# ZMOD4510.net
KiCad netlist of a schematic drawn in Altium Designer
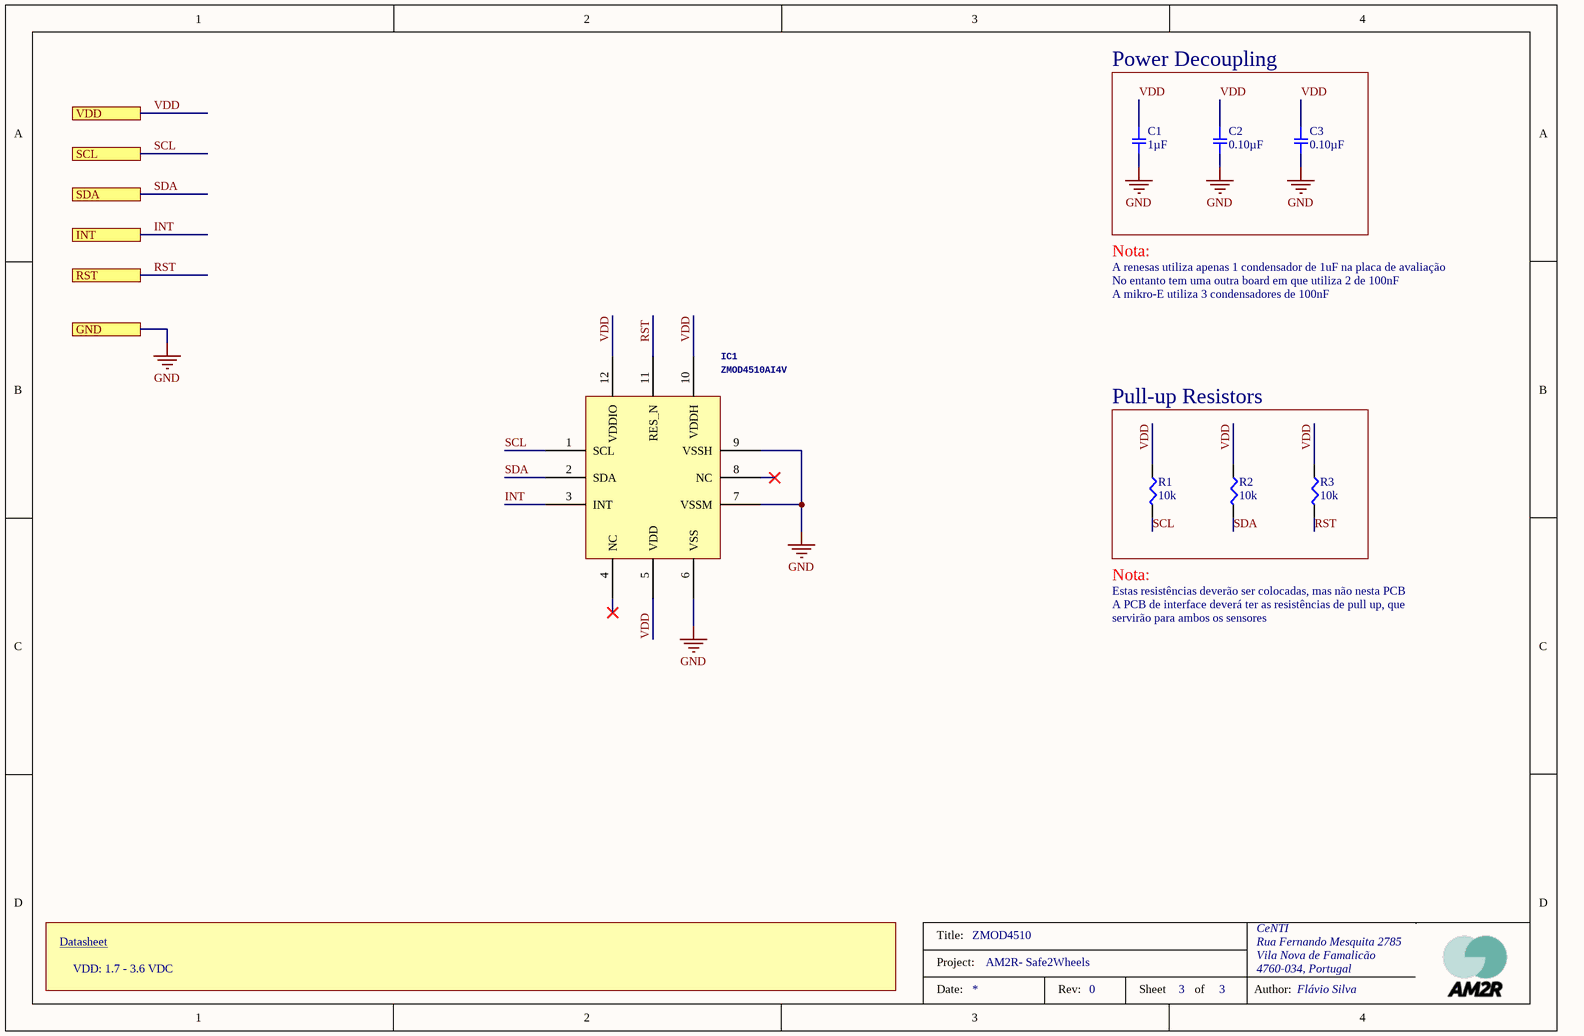
[diagram p0: ZMOD4510.SchDoc]

(export (version "E")
  (design (tool "Eeschema 10.0.6"))
  (components
    (comp (ref "C1")
      (value "1µF")
      (footprint "SMD-0402C")
      (description "CAP CER 1UF 10V X7S 0402")
      (fields
        (field (name "DIGI-KEY PART NUMBER") "490-13409-1-ND")
        (field (name "PART NUMBER") "GCM155C71A105KE38D")
      )
      (libsource (lib "capacitor_murata_0402") (part "GCM155C71A105KE38D"))
    )
    (comp (ref "C2")
      (value "0.10µF")
      (footprint "SMD-0402C")
      (description "CAP CER 0.1UF 16V X7R 0402")
      (fields
        (field (name "DIGI-KEY PART NUMBER") "490-4759-1-ND")
        (field (name "PART NUMBER") "GCM155R71C104KA55D")
      )
      (libsource (lib "capacitor_murata_0402") (part "GCM155R71C104KA55D"))
    )
    (comp (ref "C3")
      (value "0.10µF")
      (footprint "SMD-0402C")
      (description "CAP CER 0.1UF 16V X7R 0402")
      (fields
        (field (name "DIGI-KEY PART NUMBER") "490-4759-1-ND")
        (field (name "PART NUMBER") "GCM155R71C104KA55D")
      )
      (libsource (lib "capacitor_murata_0402") (part "GCM155R71C104KA55D"))
    )
    (comp (ref "IC1")
      (value "ZMOD4510AI4V")
      (footprint "ZMOD4xxx_AI4_IP67")
      (fields (field (name "MOUSER_PART_NUMBER") "972-ZMOD4510AI4V"))
      (libsource (lib "FDS") (part "ZMOD4510AI4V"))
    )
    (comp (ref "R1")
      (value "10k")
      (footprint "SMD-0402-RES")
      (description "RES SMD 10K OHM 1% 1/5W 0402")
      (fields
        (field (name "PART NUMBER") "ERJ-PA2F1002X")
        (field (name "DIGI-KEY PART NUMBER") "P17230CT-ND")
      )
      (libsource (lib "Panasonic_ERJ_0402") (part "ERJ-PA2F1002X"))
    )
    (comp (ref "R2")
      (value "10k")
      (footprint "SMD-0402-RES")
      (description "RES SMD 10K OHM 1% 1/5W 0402")
      (fields
        (field (name "PART NUMBER") "ERJ-PA2F1002X")
        (field (name "DIGI-KEY PART NUMBER") "P17230CT-ND")
      )
      (libsource (lib "Panasonic_ERJ_0402") (part "ERJ-PA2F1002X"))
    )
    (comp (ref "R3")
      (value "10k")
      (footprint "SMD-0402-RES")
      (description "RES SMD 10K OHM 1% 1/5W 0402")
      (fields
        (field (name "PART NUMBER") "ERJ-PA2F1002X")
        (field (name "DIGI-KEY PART NUMBER") "P17230CT-ND")
      )
      (libsource (lib "Panasonic_ERJ_0402") (part "ERJ-PA2F1002X"))
    )
  )
  (nets
    (net (code "1") (name "/INT") (class "Default")
      (node (ref "IC1") (pin "3") (pinfunction "INT_3") (pintype "passive"))
    )
    (net (code "2") (name "/RST") (class "Default")
      (node (ref "IC1") (pin "11") (pinfunction "RES_N_11") (pintype "passive"))
      (node (ref "R3") (pin "2") (pinfunction "2_2") (pintype "passive"))
    )
    (net (code "3") (name "/SCL") (class "Default")
      (node (ref "IC1") (pin "1") (pinfunction "SCL_1") (pintype "passive"))
      (node (ref "R1") (pin "2") (pinfunction "2_2") (pintype "passive"))
    )
    (net (code "4") (name "/SDA") (class "Default")
      (node (ref "IC1") (pin "2") (pinfunction "SDA_2") (pintype "passive"))
      (node (ref "R2") (pin "2") (pinfunction "2_2") (pintype "passive"))
    )
    (net (code "5") (name "/VDD") (class "Default")
      (node (ref "C1") (pin "1") (pinfunction "1_1") (pintype "passive"))
      (node (ref "C2") (pin "1") (pinfunction "1_1") (pintype "passive"))
      (node (ref "C3") (pin "1") (pinfunction "1_1") (pintype "passive"))
      (node (ref "IC1") (pin "10") (pinfunction "VDDH_10") (pintype "passive"))
      (node (ref "IC1") (pin "12") (pinfunction "VDDIO_12") (pintype "passive"))
      (node (ref "IC1") (pin "5") (pinfunction "VDD_5") (pintype "passive"))
      (node (ref "R1") (pin "1") (pinfunction "1_1") (pintype "passive"))
      (node (ref "R2") (pin "1") (pinfunction "1_1") (pintype "passive"))
      (node (ref "R3") (pin "1") (pinfunction "1_1") (pintype "passive"))
    )
    (net (code "6") (name "GND") (class "Default")
      (node (ref "C1") (pin "2") (pinfunction "2_2") (pintype "passive"))
      (node (ref "C2") (pin "2") (pinfunction "2_2") (pintype "passive"))
      (node (ref "C3") (pin "2") (pinfunction "2_2") (pintype "passive"))
      (node (ref "IC1") (pin "6") (pinfunction "VSS_6") (pintype "passive"))
      (node (ref "IC1") (pin "7") (pinfunction "VSSM_7") (pintype "passive"))
      (node (ref "IC1") (pin "9") (pinfunction "VSSH_9") (pintype "passive"))
    )
    (net (code "7") (name "unconnected-(IC1-NC-Pad4)") (class "Default")
      (node (ref "IC1") (pin "4") (pinfunction "NC_4") (pintype "passive+no_connect"))
    )
    (net (code "8") (name "unconnected-(IC1-NC-Pad8)") (class "Default")
      (node (ref "IC1") (pin "8") (pinfunction "NC_8") (pintype "passive+no_connect"))
    )
  )
)
